# HyperRAM2.net
KiCad netlist of a schematic drawn in Altium Designer
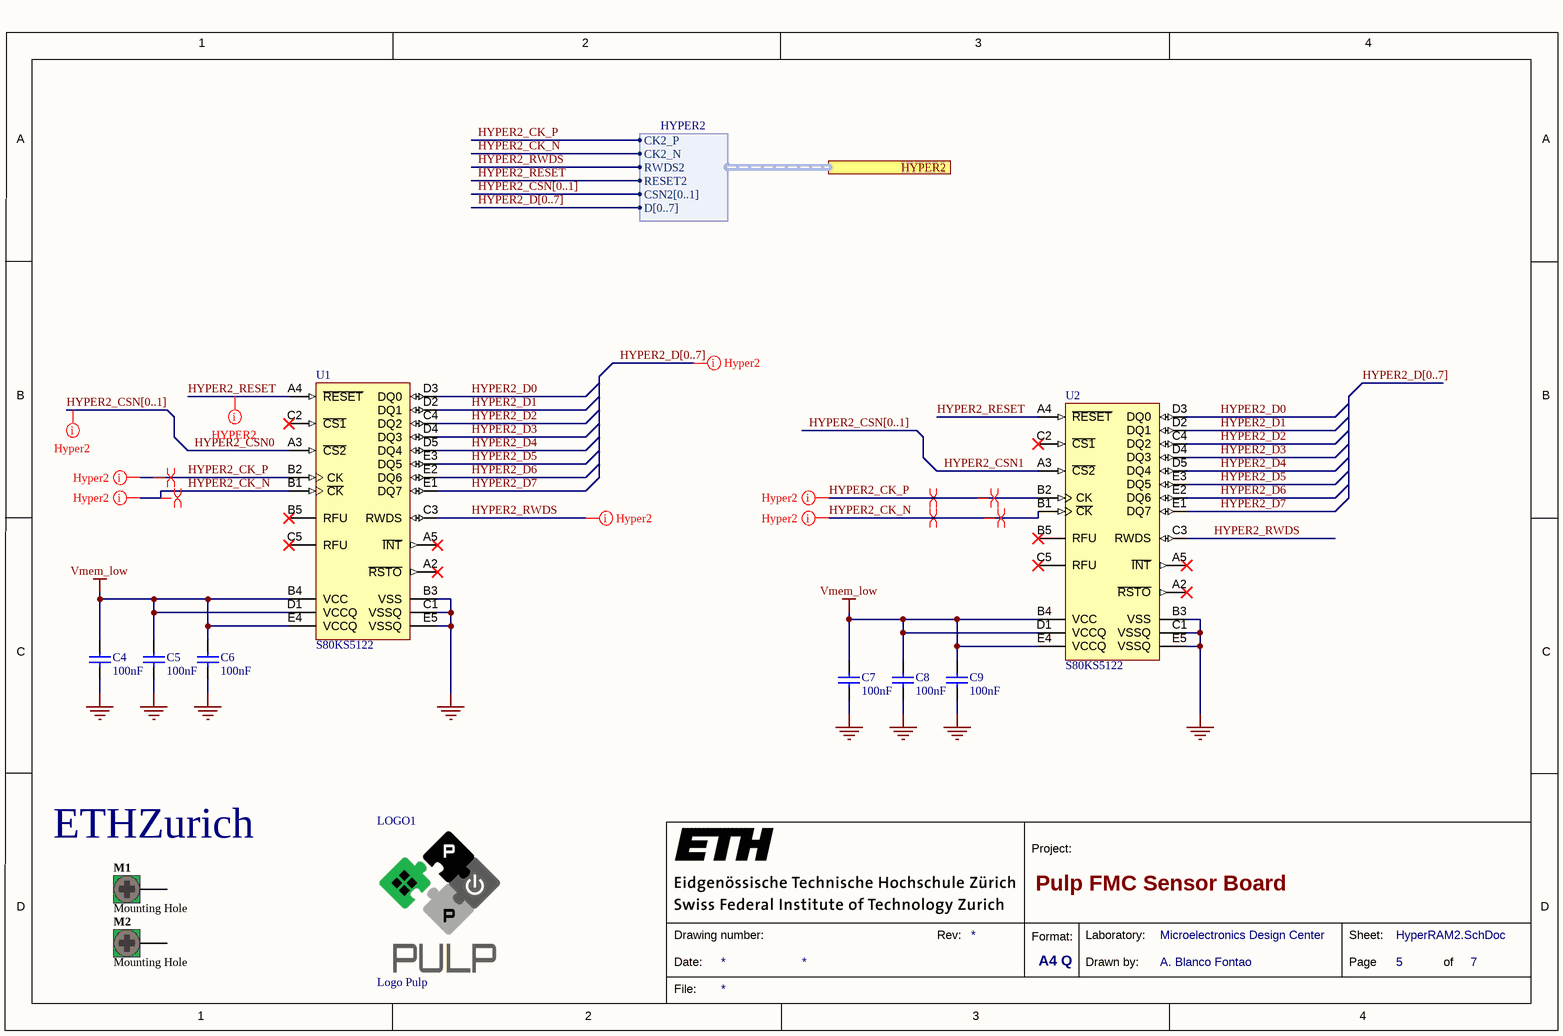
[diagram p0: HyperRAM2.SchDoc]

(export (version "E")
  (design (tool "Eeschema 10.0.6"))
  (components
    (comp (ref "A1")
      (value "Logo ETH Zurich")
      (footprint "eth-zurich_3mm")
      (libsource (lib "ETHZ Vault") (part "CMP-00038-1"))
    )
    (comp (ref "C4")
      (value "100nF")
      (footprint "CAPC0603(1608)100_N")
      (description "CAP 100nF 25V ±10% 0603 (1608 Metric) Thickness 1mm SMD")
      (fields (field (name "TOLERANCE") "Â±10%") (field (name "Comment") "CAP 100nF 25V 0603(1608)"))
      (libsource (lib "Altium Content Vault") (part "CMP-1035-02588-1"))
    )
    (comp (ref "C5")
      (value "100nF")
      (footprint "CAPC0603(1608)100_N")
      (description "CAP 100nF 25V ±10% 0603 (1608 Metric) Thickness 1mm SMD")
      (fields (field (name "TOLERANCE") "Â±10%") (field (name "Comment") "CAP 100nF 25V 0603(1608)"))
      (libsource (lib "Altium Content Vault") (part "CMP-1035-02588-1"))
    )
    (comp (ref "C6")
      (value "100nF")
      (footprint "CAPC0603(1608)100_N")
      (description "CAP 100nF 25V ±10% 0603 (1608 Metric) Thickness 1mm SMD")
      (fields (field (name "TOLERANCE") "Â±10%") (field (name "Comment") "CAP 100nF 25V 0603(1608)"))
      (libsource (lib "Altium Content Vault") (part "CMP-1035-02588-1"))
    )
    (comp (ref "C7")
      (value "100nF")
      (footprint "CAPC0603(1608)100_N")
      (description "CAP 100nF 25V ±10% 0603 (1608 Metric) Thickness 1mm SMD")
      (fields (field (name "TOLERANCE") "Â±10%") (field (name "Comment") "CAP 100nF 25V 0603(1608)"))
      (libsource (lib "Altium Content Vault") (part "CMP-1035-02588-1"))
    )
    (comp (ref "C8")
      (value "100nF")
      (footprint "CAPC0603(1608)100_N")
      (description "CAP 100nF 25V ±10% 0603 (1608 Metric) Thickness 1mm SMD")
      (fields (field (name "TOLERANCE") "Â±10%") (field (name "Comment") "CAP 100nF 25V 0603(1608)"))
      (libsource (lib "Altium Content Vault") (part "CMP-1035-02588-1"))
    )
    (comp (ref "C9")
      (value "100nF")
      (footprint "CAPC0603(1608)100_N")
      (description "CAP 100nF 25V ±10% 0603 (1608 Metric) Thickness 1mm SMD")
      (fields (field (name "TOLERANCE") "Â±10%") (field (name "Comment") "CAP 100nF 25V 0603(1608)"))
      (libsource (lib "Altium Content Vault") (part "CMP-1035-02588-1"))
    )
    (comp (ref "LOGO1")
      (value "Logo Pulp")
      (footprint "Logo Pulp")
      (description "4 Layers: only valid for layer stack as defined for the TestBoards")
      (libsource (lib "ETHZ Vault") (part "CMP-00145-1"))
    )
    (comp (ref "M1")
      (value "Mounting Hole")
      (footprint "Hole M3")
      (description "Mounting Hole, 7.2mm pad, 3.2mm plated hole")
      (libsource (lib "ETHZ Vault") (part "Hole"))
    )
    (comp (ref "M2")
      (value "Mounting Hole")
      (footprint "Hole M3")
      (description "Mounting Hole, 7.2mm pad, 3.2mm plated hole")
      (libsource (lib "ETHZ Vault") (part "Hole"))
    )
    (comp (ref "U1")
      (value "S80KS5122")
      (footprint "FBGA24_A-130")
      (description "512 Mb: HYPERRAM™ self-refresh dynamic\r\n RAM (DRAM) with HYPERBUS™ interface\r\n 1.8 V")
      (fields (field (name "MANUFACTURER") "Cypress Semiconductor Corp"))
      (libsource (lib "Pulp FMC Sensor Board") (part "CMP-00514-1"))
    )
    (comp (ref "U2")
      (value "S80KS5122")
      (footprint "FBGA24_A-130")
      (description "512 Mb: HYPERRAM™ self-refresh dynamic\r\n RAM (DRAM) with HYPERBUS™ interface\r\n 1.8 V")
      (fields (field (name "MANUFACTURER") "Cypress Semiconductor Corp"))
      (libsource (lib "Pulp FMC Sensor Board") (part "CMP-00514-1"))
    )
  )
  (nets
    (net (code "2") (name "/HYPER2_CK_N") (class "Default")
      (node (ref "U1") (pin "B1") (pinfunction "~{CK}_B1") (pintype "input"))
      (node (ref "U2") (pin "B1") (pinfunction "~{CK}_B1") (pintype "input"))
    )
    (net (code "3") (name "/HYPER2_CK_P") (class "Default")
      (node (ref "U1") (pin "B2") (pinfunction "CK_B2") (pintype "input"))
      (node (ref "U2") (pin "B2") (pinfunction "CK_B2") (pintype "input"))
    )
    (net (code "4") (name "/HYPER2_CSN0") (class "Default")
      (node (ref "U1") (pin "A3") (pinfunction "~{CS2}_A3") (pintype "input"))
    )
    (net (code "5") (name "/HYPER2_CSN1") (class "Default")
      (node (ref "U2") (pin "A3") (pinfunction "~{CS2}_A3") (pintype "input"))
    )
    (net (code "7") (name "/HYPER2_D0") (class "Default")
      (node (ref "U1") (pin "D3") (pinfunction "DQ0_D3") (pintype "bidirectional"))
      (node (ref "U2") (pin "D3") (pinfunction "DQ0_D3") (pintype "bidirectional"))
    )
    (net (code "8") (name "/HYPER2_D1") (class "Default")
      (node (ref "U1") (pin "D2") (pinfunction "DQ1_D2") (pintype "bidirectional"))
      (node (ref "U2") (pin "D2") (pinfunction "DQ1_D2") (pintype "bidirectional"))
    )
    (net (code "9") (name "/HYPER2_D2") (class "Default")
      (node (ref "U1") (pin "C4") (pinfunction "DQ2_C4") (pintype "bidirectional"))
      (node (ref "U2") (pin "C4") (pinfunction "DQ2_C4") (pintype "bidirectional"))
    )
    (net (code "10") (name "/HYPER2_D3") (class "Default")
      (node (ref "U1") (pin "D4") (pinfunction "DQ3_D4") (pintype "bidirectional"))
      (node (ref "U2") (pin "D4") (pinfunction "DQ3_D4") (pintype "bidirectional"))
    )
    (net (code "11") (name "/HYPER2_D4") (class "Default")
      (node (ref "U1") (pin "D5") (pinfunction "DQ4_D5") (pintype "bidirectional"))
      (node (ref "U2") (pin "D5") (pinfunction "DQ4_D5") (pintype "bidirectional"))
    )
    (net (code "12") (name "/HYPER2_D5") (class "Default")
      (node (ref "U1") (pin "E3") (pinfunction "DQ5_E3") (pintype "bidirectional"))
      (node (ref "U2") (pin "E3") (pinfunction "DQ5_E3") (pintype "bidirectional"))
    )
    (net (code "13") (name "/HYPER2_D6") (class "Default")
      (node (ref "U1") (pin "E2") (pinfunction "DQ6_E2") (pintype "bidirectional"))
      (node (ref "U2") (pin "E2") (pinfunction "DQ6_E2") (pintype "bidirectional"))
    )
    (net (code "14") (name "/HYPER2_D7") (class "Default")
      (node (ref "U1") (pin "E1") (pinfunction "DQ7_E1") (pintype "bidirectional"))
      (node (ref "U2") (pin "E1") (pinfunction "DQ7_E1") (pintype "bidirectional"))
    )
    (net (code "16") (name "/HYPER2_RESET") (class "Default")
      (node (ref "U1") (pin "A4") (pinfunction "~{RESET}_A4") (pintype "input"))
      (node (ref "U2") (pin "A4") (pinfunction "~{RESET}_A4") (pintype "input"))
    )
    (net (code "17") (name "/HYPER2_RWDS") (class "Default")
      (node (ref "U1") (pin "C3") (pinfunction "RWDS_C3") (pintype "bidirectional"))
      (node (ref "U2") (pin "C3") (pinfunction "RWDS_C3") (pintype "bidirectional"))
    )
    (net (code "19") (name "GND") (class "Default")
      (node (ref "C4") (pin "1") (pinfunction "1_1") (pintype "passive"))
      (node (ref "C5") (pin "1") (pinfunction "1_1") (pintype "passive"))
      (node (ref "C6") (pin "1") (pinfunction "1_1") (pintype "passive"))
      (node (ref "C7") (pin "1") (pinfunction "1_1") (pintype "passive"))
      (node (ref "C8") (pin "1") (pinfunction "1_1") (pintype "passive"))
      (node (ref "C9") (pin "1") (pinfunction "1_1") (pintype "passive"))
      (node (ref "U1") (pin "B3") (pinfunction "VSS_B3") (pintype "power_in"))
      (node (ref "U1") (pin "C1") (pinfunction "VSSQ_C1") (pintype "power_in"))
      (node (ref "U1") (pin "E5") (pinfunction "VSSQ_E5") (pintype "power_in"))
      (node (ref "U2") (pin "B3") (pinfunction "VSS_B3") (pintype "power_in"))
      (node (ref "U2") (pin "C1") (pinfunction "VSSQ_C1") (pintype "power_in"))
      (node (ref "U2") (pin "E5") (pinfunction "VSSQ_E5") (pintype "power_in"))
    )
    (net (code "20") (name "Vmem_low") (class "Default")
      (node (ref "C4") (pin "2") (pinfunction "2_2") (pintype "passive"))
      (node (ref "C5") (pin "2") (pinfunction "2_2") (pintype "passive"))
      (node (ref "C6") (pin "2") (pinfunction "2_2") (pintype "passive"))
      (node (ref "C7") (pin "2") (pinfunction "2_2") (pintype "passive"))
      (node (ref "C8") (pin "2") (pinfunction "2_2") (pintype "passive"))
      (node (ref "C9") (pin "2") (pinfunction "2_2") (pintype "passive"))
      (node (ref "U1") (pin "B4") (pinfunction "VCC_B4") (pintype "power_in"))
      (node (ref "U1") (pin "D1") (pinfunction "VCCQ_D1") (pintype "power_in"))
      (node (ref "U1") (pin "E4") (pinfunction "VCCQ_E4") (pintype "power_in"))
      (node (ref "U2") (pin "B4") (pinfunction "VCC_B4") (pintype "power_in"))
      (node (ref "U2") (pin "D1") (pinfunction "VCCQ_D1") (pintype "power_in"))
      (node (ref "U2") (pin "E4") (pinfunction "VCCQ_E4") (pintype "power_in"))
    )
    (net (code "21") (name "unconnected-(M1-Pad1)") (class "Default")
      (node (ref "M1") (pin "1") (pinfunction "1_1") (pintype "passive"))
    )
    (net (code "22") (name "unconnected-(M2-Pad1)") (class "Default")
      (node (ref "M2") (pin "1") (pinfunction "1_1") (pintype "passive"))
    )
    (net (code "23") (name "unconnected-(U1-RFU-PadB5)") (class "Default")
      (node (ref "U1") (pin "B5") (pinfunction "RFU_B5") (pintype "passive+no_connect"))
    )
    (net (code "24") (name "unconnected-(U1-RFU-PadC5)") (class "Default")
      (node (ref "U1") (pin "C5") (pinfunction "RFU_C5") (pintype "passive+no_connect"))
    )
    (net (code "25") (name "unconnected-(U1-~{CS1}-PadC2)") (class "Default")
      (node (ref "U1") (pin "C2") (pinfunction "~{CS1}_C2") (pintype "input+no_connect"))
    )
    (net (code "26") (name "unconnected-(U1-~{INT}-PadA5)") (class "Default")
      (node (ref "U1") (pin "A5") (pinfunction "~{INT}_A5") (pintype "output+no_connect"))
    )
    (net (code "27") (name "unconnected-(U1-~{RSTO}-PadA2)") (class "Default")
      (node (ref "U1") (pin "A2") (pinfunction "~{RSTO}_A2") (pintype "output+no_connect"))
    )
    (net (code "28") (name "unconnected-(U2-RFU-PadB5)") (class "Default")
      (node (ref "U2") (pin "B5") (pinfunction "RFU_B5") (pintype "passive+no_connect"))
    )
    (net (code "29") (name "unconnected-(U2-RFU-PadC5)") (class "Default")
      (node (ref "U2") (pin "C5") (pinfunction "RFU_C5") (pintype "passive+no_connect"))
    )
    (net (code "30") (name "unconnected-(U2-~{CS1}-PadC2)") (class "Default")
      (node (ref "U2") (pin "C2") (pinfunction "~{CS1}_C2") (pintype "input+no_connect"))
    )
    (net (code "31") (name "unconnected-(U2-~{INT}-PadA5)") (class "Default")
      (node (ref "U2") (pin "A5") (pinfunction "~{INT}_A5") (pintype "output+no_connect"))
    )
    (net (code "32") (name "unconnected-(U2-~{RSTO}-PadA2)") (class "Default")
      (node (ref "U2") (pin "A2") (pinfunction "~{RSTO}_A2") (pintype "output+no_connect"))
    )
  )
)
